# board.net
KiCad netlist of a schematic drawn in EAGLE
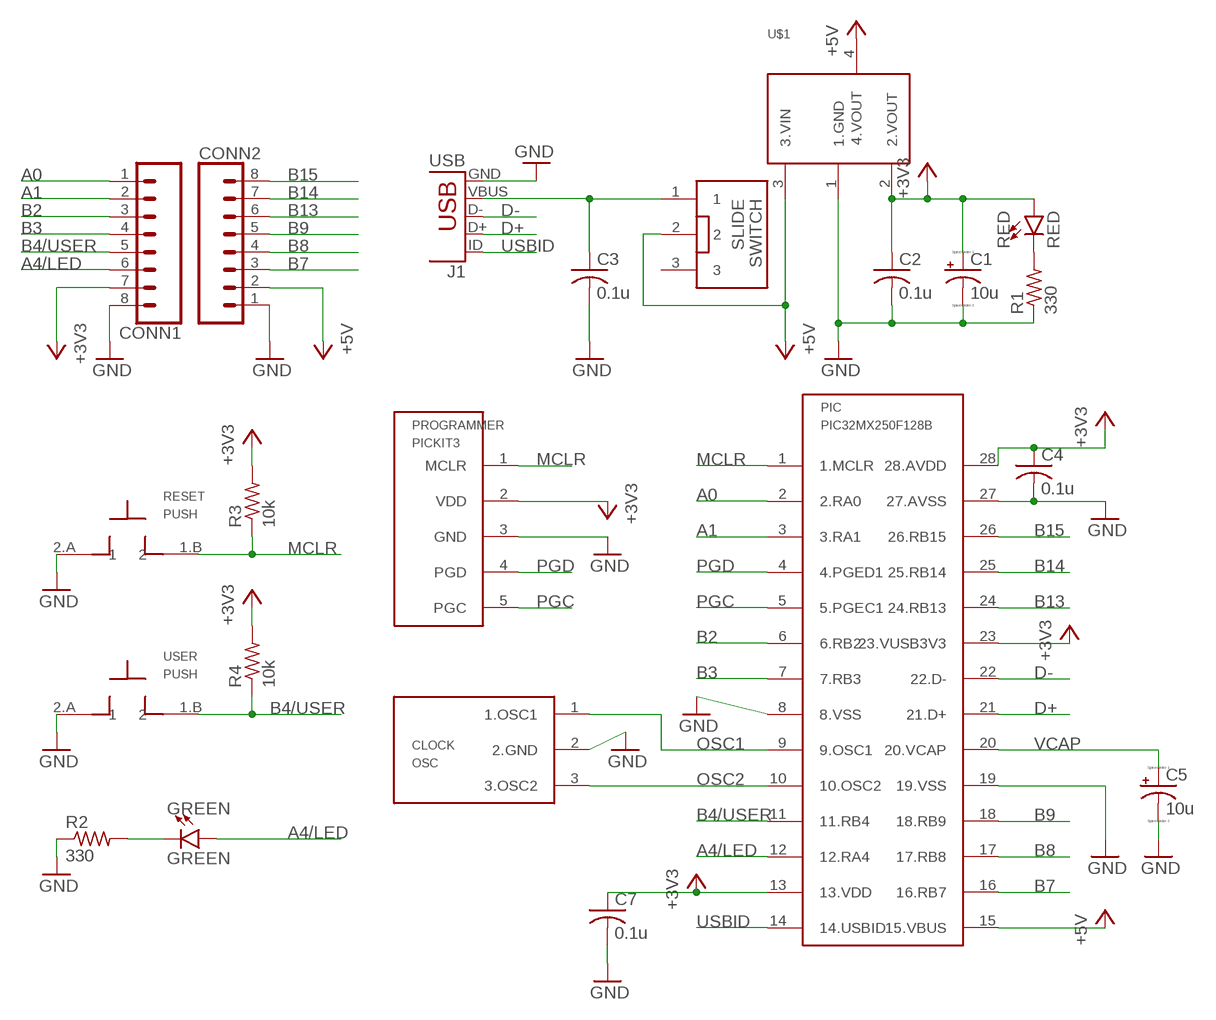
[diagram p0: schematic, sheet 1]

(export (version "E")
  (design (tool "Eeschema 10.0.6"))
  (components
    (comp (ref "C1")
      (value "10u")
      (footprint "eagle-import:CAP-POL-0603")
      (libsource (lib "eagle-import") (part "CAP-POL"))
    )
    (comp (ref "C2")
      (value "0.1u")
      (footprint "eagle-import:C0603")
      (libsource (lib "eagle-import") (part "C-USC0603"))
    )
    (comp (ref "C3")
      (value "0.1u")
      (footprint "eagle-import:C0603")
      (libsource (lib "eagle-import") (part "C-USC0603"))
    )
    (comp (ref "C4")
      (value "0.1u")
      (footprint "eagle-import:C0603")
      (libsource (lib "eagle-import") (part "C-USC0603"))
    )
    (comp (ref "C5")
      (value "10u")
      (footprint "eagle-import:CAP-POL-0603")
      (fields (field (name "SPICEPREFIX") "C"))
      (libsource (lib "eagle-import") (part "CAP-POL"))
    )
    (comp (ref "C7")
      (value "0.1u")
      (footprint "eagle-import:C0603")
      (libsource (lib "eagle-import") (part "C-USC0603"))
    )
    (comp (ref "CLOCK")
      (value "OSC")
      (footprint "eagle-import:NU32V7_RESONATOR-SMD")
      (libsource (lib "eagle-import") (part "OSC"))
    )
    (comp (ref "CONN1")
      (value "CONN_08\"")
      (footprint "eagle-import:1X08")
      (libsource (lib "eagle-import") (part "CONN_08{dblquote}"))
    )
    (comp (ref "CONN2")
      (value "CONN_08\"")
      (footprint "eagle-import:1X08")
      (libsource (lib "eagle-import") (part "CONN_08{dblquote}"))
    )
    (comp (ref "GREEN")
      (value "GREEN")
      (footprint "eagle-import:LED-0603")
      (libsource (lib "eagle-import") (part "LED-GREEN0603"))
    )
    (comp (ref "J1")
      (value "USB")
      (footprint "eagle-import:NU32V7_USB-MINIB")
      (fields (field (name "SPICEPREFIX") "X"))
      (libsource (lib "eagle-import") (part "USB"))
    )
    (comp (ref "PIC")
      (value "PIC32MX250F128B")
      (footprint "eagle-import:DIL28-3")
      (libsource (lib "eagle-import") (part "PIC32MX250F128B"))
    )
    (comp (ref "PROGRAMMER")
      (value "PICKIT3")
      (footprint "eagle-import:1X05")
      (libsource (lib "eagle-import") (part "PICKIT3"))
    )
    (comp (ref "R1")
      (value "330")
      (footprint "eagle-import:R0603")
      (fields (field (name "SPICEPREFIX") "R"))
      (libsource (lib "eagle-import") (part "R-US_R0603"))
    )
    (comp (ref "R2")
      (value "330")
      (footprint "eagle-import:R0603")
      (libsource (lib "eagle-import") (part "R-US_R0603"))
    )
    (comp (ref "R3")
      (value "10k")
      (footprint "eagle-import:R0603")
      (libsource (lib "eagle-import") (part "R-US_R0603"))
    )
    (comp (ref "R4")
      (value "10k")
      (footprint "eagle-import:R0603")
      (libsource (lib "eagle-import") (part "R-US_R0603"))
    )
    (comp (ref "RED")
      (value "RED")
      (footprint "eagle-import:LED-0603")
      (fields (field (name "SPICEPREFIX") "R"))
      (libsource (lib "eagle-import") (part "LED-RED0603"))
    )
    (comp (ref "RESET")
      (value "PUSH")
      (footprint "eagle-import:NU32V7_MOM_SW")
      (libsource (lib "eagle-import") (part "PUSH"))
    )
    (comp (ref "SWITCH")
      (value "SLIDE")
      (footprint "eagle-import:SLIDE")
      (fields (field (name "SPICEPREFIX") "J"))
      (libsource (lib "eagle-import") (part "SLIDE"))
    )
    (comp (ref "U$1")
      (value "SOT-223")
      (footprint "eagle-import:NU32V7_SOT223")
      (libsource (lib "eagle-import") (part "SOT-223"))
    )
    (comp (ref "USER")
      (value "PUSH")
      (footprint "eagle-import:NU32V7_MOM_SW")
      (libsource (lib "eagle-import") (part "PUSH"))
    )
  )
  (nets
    (net (code "1") (name "+3V3") (class "Default")
      (node (ref "C1") (pin "1") (pinfunction "+_1") (pintype "passive"))
      (node (ref "C2") (pin "1") (pinfunction "1_1") (pintype "passive"))
      (node (ref "C4") (pin "1") (pinfunction "1_1") (pintype "passive"))
      (node (ref "C7") (pin "1") (pinfunction "1_1") (pintype "passive"))
      (node (ref "CONN1") (pin "7") (pinfunction "7_7") (pintype "passive"))
      (node (ref "PIC") (pin "13") (pinfunction "13.VDD_13") (pintype "bidirectional"))
      (node (ref "PIC") (pin "23") (pinfunction "23.VUSB3V3_23") (pintype "bidirectional"))
      (node (ref "PIC") (pin "28") (pinfunction "28.AVDD_28") (pintype "bidirectional"))
      (node (ref "PROGRAMMER") (pin "2") (pinfunction "VDD_2") (pintype "bidirectional"))
      (node (ref "R3") (pin "2") (pinfunction "2_2") (pintype "passive"))
      (node (ref "R4") (pin "2") (pinfunction "2_2") (pintype "passive"))
      (node (ref "RED") (pin "A") (pinfunction "A_A") (pintype "passive"))
      (node (ref "U$1") (pin "2") (pinfunction "2.VOUT_2") (pintype "bidirectional"))
    )
    (net (code "2") (name "+5V") (class "Default")
      (node (ref "CONN2") (pin "2") (pinfunction "2_2") (pintype "passive"))
      (node (ref "PIC") (pin "15") (pinfunction "15.VBUS_15") (pintype "bidirectional"))
      (node (ref "SWITCH") (pin "2") (pinfunction "2_2") (pintype "bidirectional"))
      (node (ref "U$1") (pin "3") (pinfunction "3.VIN_3") (pintype "bidirectional"))
      (node (ref "U$1") (pin "4") (pinfunction "4.VOUT_4") (pintype "bidirectional"))
    )
    (net (code "3") (name "/A0") (class "Default")
      (node (ref "CONN1") (pin "1") (pinfunction "1_1") (pintype "passive"))
      (node (ref "PIC") (pin "2") (pinfunction "2.RA0_2") (pintype "bidirectional"))
    )
    (net (code "4") (name "/A1") (class "Default")
      (node (ref "CONN1") (pin "2") (pinfunction "2_2") (pintype "passive"))
      (node (ref "PIC") (pin "3") (pinfunction "3.RA1_3") (pintype "bidirectional"))
    )
    (net (code "5") (name "/A4{slash}LED") (class "Default")
      (node (ref "CONN1") (pin "6") (pinfunction "6_6") (pintype "passive"))
      (node (ref "GREEN") (pin "A") (pinfunction "A_A") (pintype "passive"))
      (node (ref "PIC") (pin "12") (pinfunction "12.RA4_12") (pintype "bidirectional"))
    )
    (net (code "6") (name "/B2") (class "Default")
      (node (ref "CONN1") (pin "3") (pinfunction "3_3") (pintype "passive"))
      (node (ref "PIC") (pin "6") (pinfunction "6.RB2_6") (pintype "bidirectional"))
    )
    (net (code "7") (name "/B3") (class "Default")
      (node (ref "CONN1") (pin "4") (pinfunction "4_4") (pintype "passive"))
      (node (ref "PIC") (pin "7") (pinfunction "7.RB3_7") (pintype "bidirectional"))
    )
    (net (code "8") (name "/B4{slash}USER") (class "Default")
      (node (ref "CONN1") (pin "5") (pinfunction "5_5") (pintype "passive"))
      (node (ref "PIC") (pin "11") (pinfunction "11.RB4_11") (pintype "bidirectional"))
      (node (ref "R4") (pin "1") (pinfunction "1_1") (pintype "passive"))
      (node (ref "USER") (pin "1.B") (pinfunction "2_1.B") (pintype "bidirectional"))
    )
    (net (code "9") (name "/B7") (class "Default")
      (node (ref "CONN2") (pin "3") (pinfunction "3_3") (pintype "passive"))
      (node (ref "PIC") (pin "16") (pinfunction "16.RB7_16") (pintype "bidirectional"))
    )
    (net (code "10") (name "/B8") (class "Default")
      (node (ref "CONN2") (pin "4") (pinfunction "4_4") (pintype "passive"))
      (node (ref "PIC") (pin "17") (pinfunction "17.RB8_17") (pintype "bidirectional"))
    )
    (net (code "11") (name "/B9") (class "Default")
      (node (ref "CONN2") (pin "5") (pinfunction "5_5") (pintype "passive"))
      (node (ref "PIC") (pin "18") (pinfunction "18.RB9_18") (pintype "bidirectional"))
    )
    (net (code "12") (name "/B13") (class "Default")
      (node (ref "CONN2") (pin "6") (pinfunction "6_6") (pintype "passive"))
      (node (ref "PIC") (pin "24") (pinfunction "24.RB13_24") (pintype "bidirectional"))
    )
    (net (code "13") (name "/B14") (class "Default")
      (node (ref "CONN2") (pin "7") (pinfunction "7_7") (pintype "passive"))
      (node (ref "PIC") (pin "25") (pinfunction "25.RB14_25") (pintype "bidirectional"))
    )
    (net (code "14") (name "/B15") (class "Default")
      (node (ref "CONN2") (pin "8") (pinfunction "8_8") (pintype "passive"))
      (node (ref "PIC") (pin "26") (pinfunction "26.RB15_26") (pintype "bidirectional"))
    )
    (net (code "15") (name "/D+") (class "Default")
      (node (ref "J1") (pin "D+") (pinfunction "D+_D+") (pintype "bidirectional"))
      (node (ref "PIC") (pin "21") (pinfunction "21.D+_21") (pintype "bidirectional"))
    )
    (net (code "16") (name "/D-") (class "Default")
      (node (ref "J1") (pin "D-") (pinfunction "D-_D-") (pintype "bidirectional"))
      (node (ref "PIC") (pin "22") (pinfunction "22.D-_22") (pintype "bidirectional"))
    )
    (net (code "17") (name "/MCLR") (class "Default")
      (node (ref "PIC") (pin "1") (pinfunction "1.MCLR_1") (pintype "bidirectional"))
      (node (ref "PROGRAMMER") (pin "1") (pinfunction "MCLR_1") (pintype "bidirectional"))
      (node (ref "R3") (pin "1") (pinfunction "1_1") (pintype "passive"))
      (node (ref "RESET") (pin "1.B") (pinfunction "2_1.B") (pintype "bidirectional"))
    )
    (net (code "18") (name "/OSC1") (class "Default")
      (node (ref "CLOCK") (pin "1") (pinfunction "1.OSC1_1") (pintype "bidirectional"))
      (node (ref "PIC") (pin "9") (pinfunction "9.OSC1_9") (pintype "bidirectional"))
    )
    (net (code "19") (name "/OSC2") (class "Default")
      (node (ref "CLOCK") (pin "3") (pinfunction "3.OSC2_3") (pintype "bidirectional"))
      (node (ref "PIC") (pin "10") (pinfunction "10.OSC2_10") (pintype "bidirectional"))
    )
    (net (code "20") (name "/PGC") (class "Default")
      (node (ref "PIC") (pin "5") (pinfunction "5.PGEC1_5") (pintype "bidirectional"))
      (node (ref "PROGRAMMER") (pin "5") (pinfunction "PGC_5") (pintype "bidirectional"))
    )
    (net (code "21") (name "/PGD") (class "Default")
      (node (ref "PIC") (pin "4") (pinfunction "4.PGED1_4") (pintype "bidirectional"))
      (node (ref "PROGRAMMER") (pin "4") (pinfunction "PGD_4") (pintype "bidirectional"))
    )
    (net (code "22") (name "/USBID") (class "Default")
      (node (ref "J1") (pin "ID") (pinfunction "ID_ID") (pintype "bidirectional"))
      (node (ref "PIC") (pin "14") (pinfunction "14.USBID_14") (pintype "bidirectional"))
    )
    (net (code "23") (name "/VCAP") (class "Default")
      (node (ref "C5") (pin "1") (pinfunction "+_1") (pintype "passive"))
      (node (ref "PIC") (pin "20") (pinfunction "20.VCAP_20") (pintype "bidirectional"))
    )
    (net (code "24") (name "GND") (class "Default")
      (node (ref "C1") (pin "2") (pinfunction "-_2") (pintype "passive"))
      (node (ref "C2") (pin "2") (pinfunction "2_2") (pintype "passive"))
      (node (ref "C3") (pin "2") (pinfunction "2_2") (pintype "passive"))
      (node (ref "C4") (pin "2") (pinfunction "2_2") (pintype "passive"))
      (node (ref "C5") (pin "2") (pinfunction "-_2") (pintype "passive"))
      (node (ref "C7") (pin "2") (pinfunction "2_2") (pintype "passive"))
      (node (ref "CLOCK") (pin "2") (pinfunction "2.GND_2") (pintype "bidirectional"))
      (node (ref "CONN1") (pin "8") (pinfunction "8_8") (pintype "passive"))
      (node (ref "CONN2") (pin "1") (pinfunction "1_1") (pintype "passive"))
      (node (ref "J1") (pin "GND") (pinfunction "GND_GND") (pintype "bidirectional"))
      (node (ref "PIC") (pin "19") (pinfunction "19.VSS_19") (pintype "bidirectional"))
      (node (ref "PIC") (pin "27") (pinfunction "27.AVSS_27") (pintype "bidirectional"))
      (node (ref "PIC") (pin "8") (pinfunction "8.VSS_8") (pintype "bidirectional"))
      (node (ref "PROGRAMMER") (pin "3") (pinfunction "GND_3") (pintype "bidirectional"))
      (node (ref "R1") (pin "1") (pinfunction "1_1") (pintype "passive"))
      (node (ref "R2") (pin "1") (pinfunction "1_1") (pintype "passive"))
      (node (ref "RESET") (pin "2.A") (pinfunction "1_2.A") (pintype "bidirectional"))
      (node (ref "U$1") (pin "1") (pinfunction "1.GND_1") (pintype "bidirectional"))
      (node (ref "USER") (pin "2.A") (pinfunction "1_2.A") (pintype "bidirectional"))
    )
    (net (code "25") (name "Net-(C3-Pad1)") (class "Default")
      (node (ref "C3") (pin "1") (pinfunction "1_1") (pintype "passive"))
      (node (ref "J1") (pin "VBUS") (pinfunction "VBUS_VBUS") (pintype "bidirectional"))
      (node (ref "SWITCH") (pin "1") (pinfunction "1_1") (pintype "bidirectional"))
    )
    (net (code "26") (name "Net-(GREEN-PadC)") (class "Default")
      (node (ref "GREEN") (pin "C") (pinfunction "C_C") (pintype "passive"))
      (node (ref "R2") (pin "2") (pinfunction "2_2") (pintype "passive"))
    )
    (net (code "27") (name "Net-(R1-Pad2)") (class "Default")
      (node (ref "R1") (pin "2") (pinfunction "2_2") (pintype "passive"))
      (node (ref "RED") (pin "C") (pinfunction "C_C") (pintype "passive"))
    )
    (net (code "28") (name "unconnected-(SWITCH-Pad3)") (class "Default")
      (node (ref "SWITCH") (pin "3") (pinfunction "3_3") (pintype "bidirectional"))
    )
  )
)
